# version_1_3.net
KiCad netlist of a schematic drawn in EAGLE
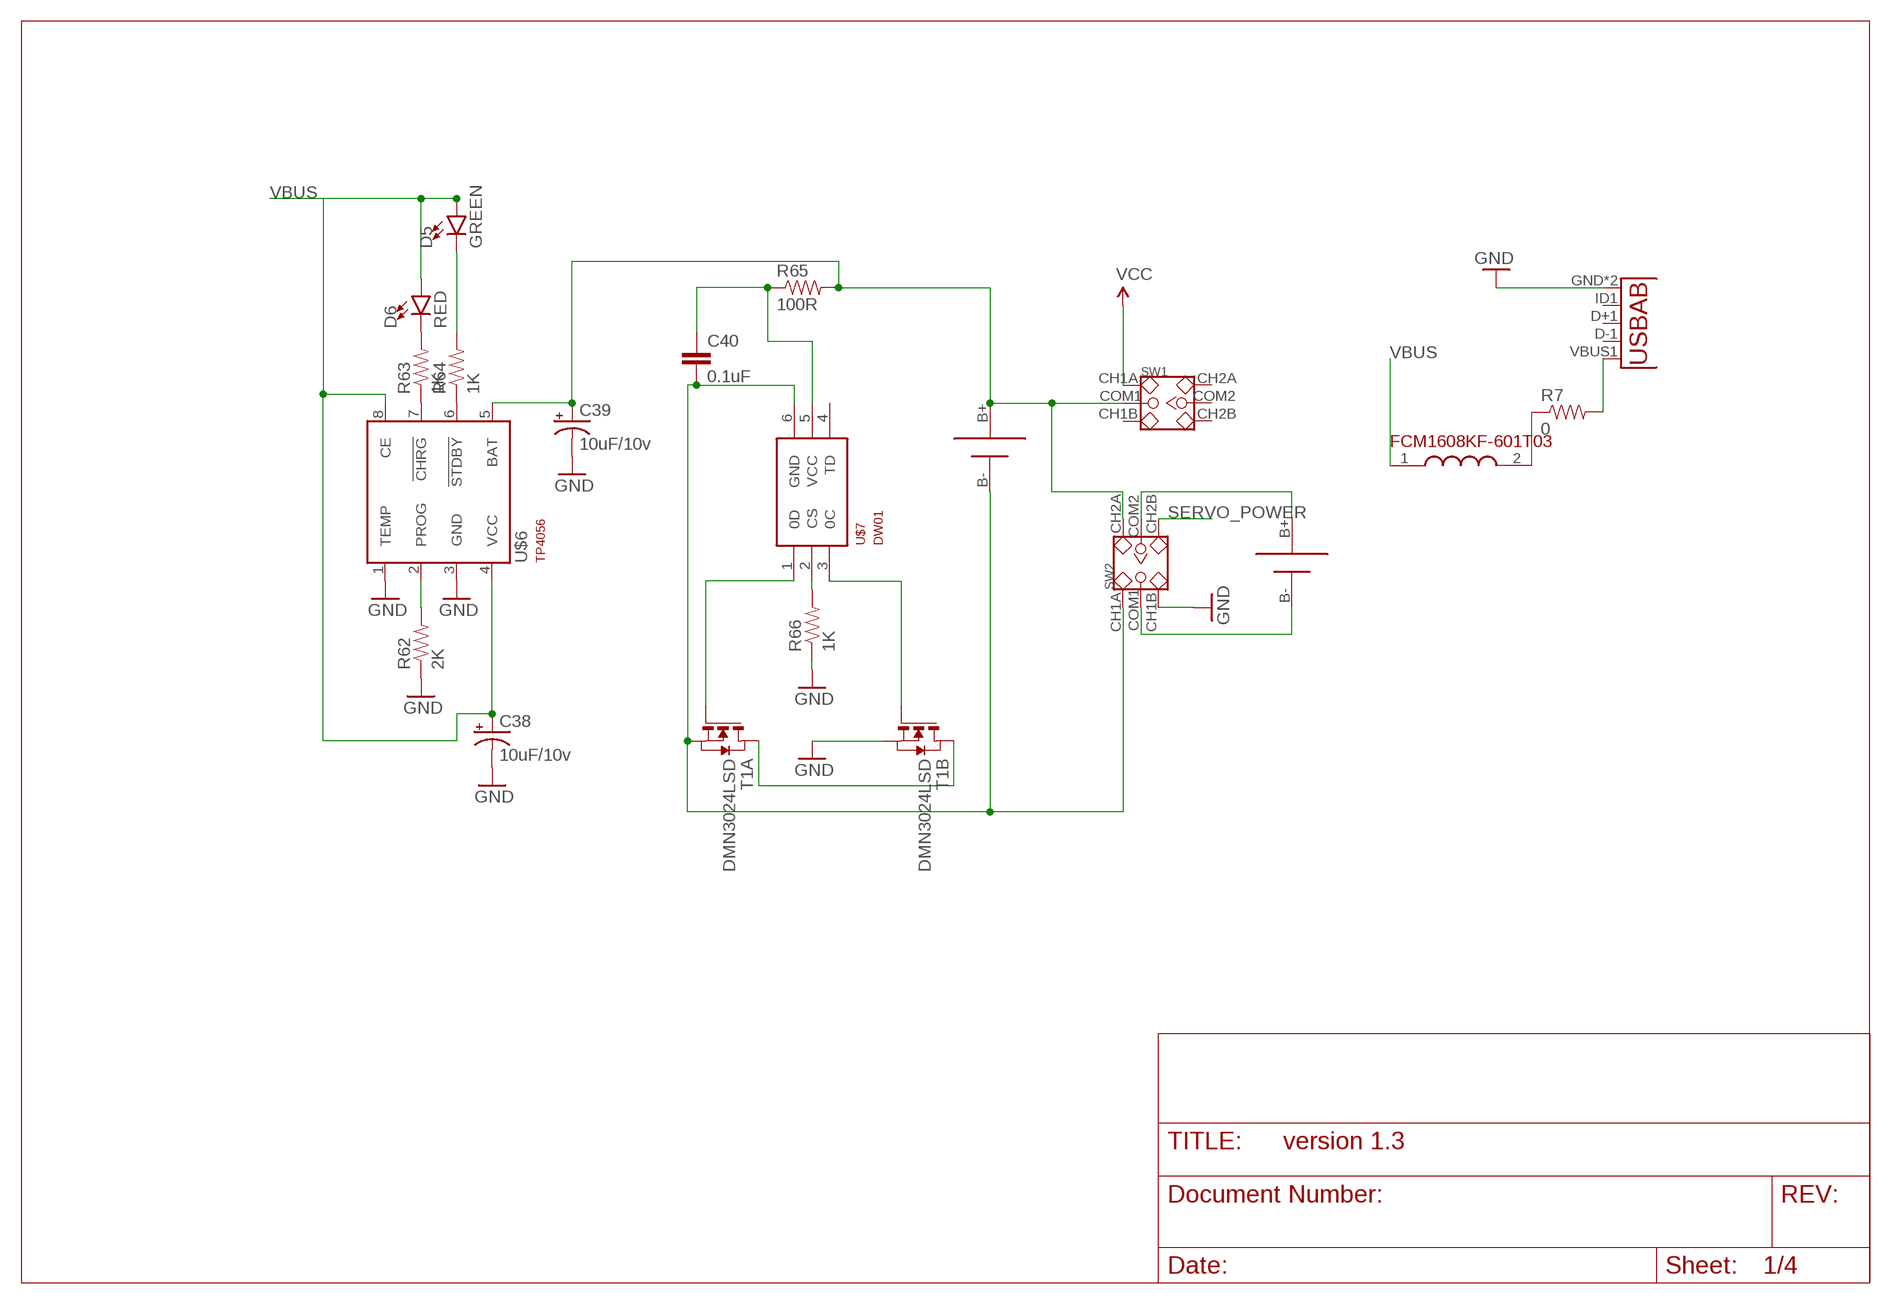
[diagram p0: schematic, sheet 1]
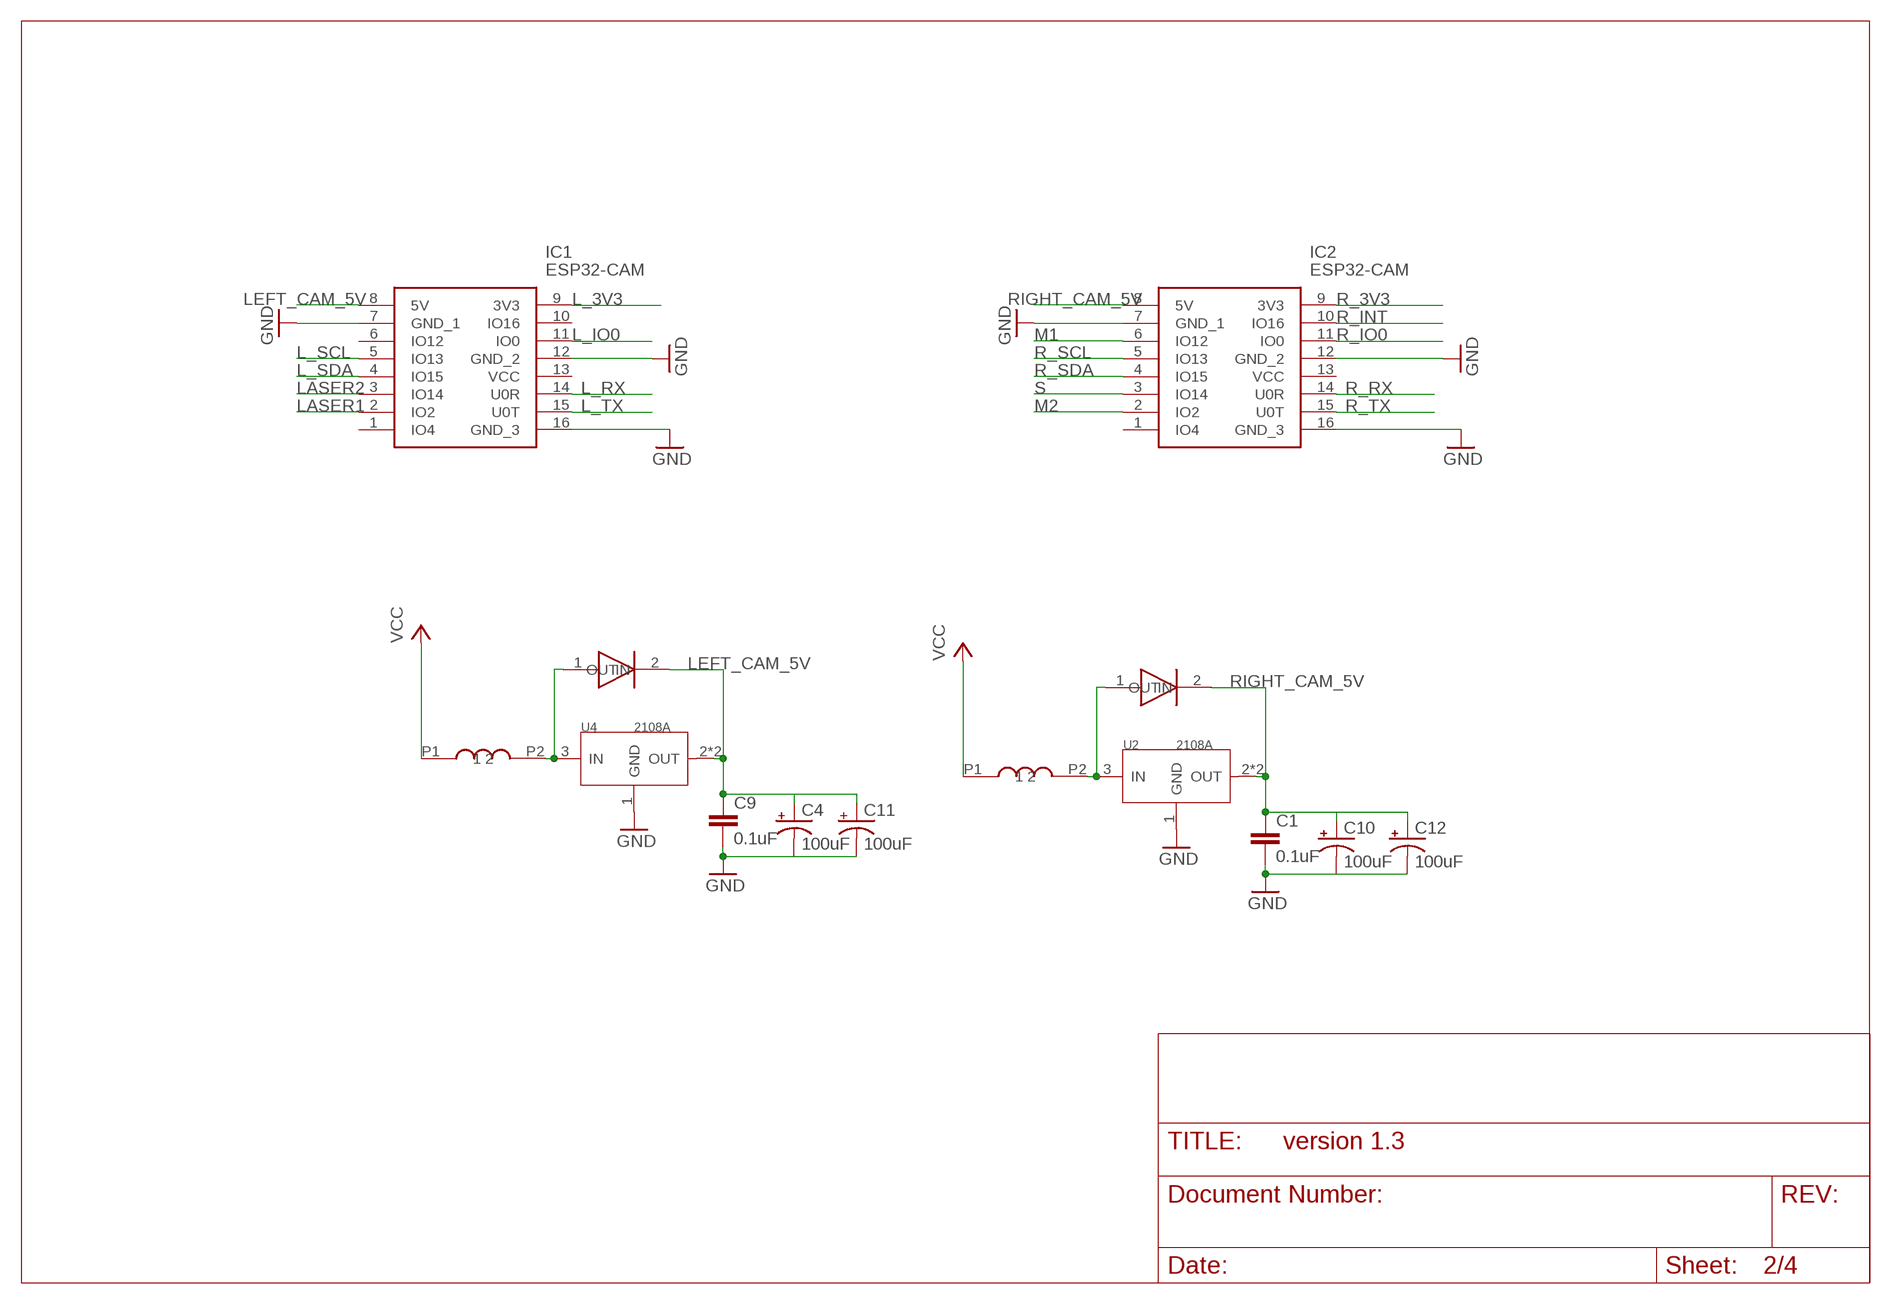
[diagram p1: schematic, sheet 2]
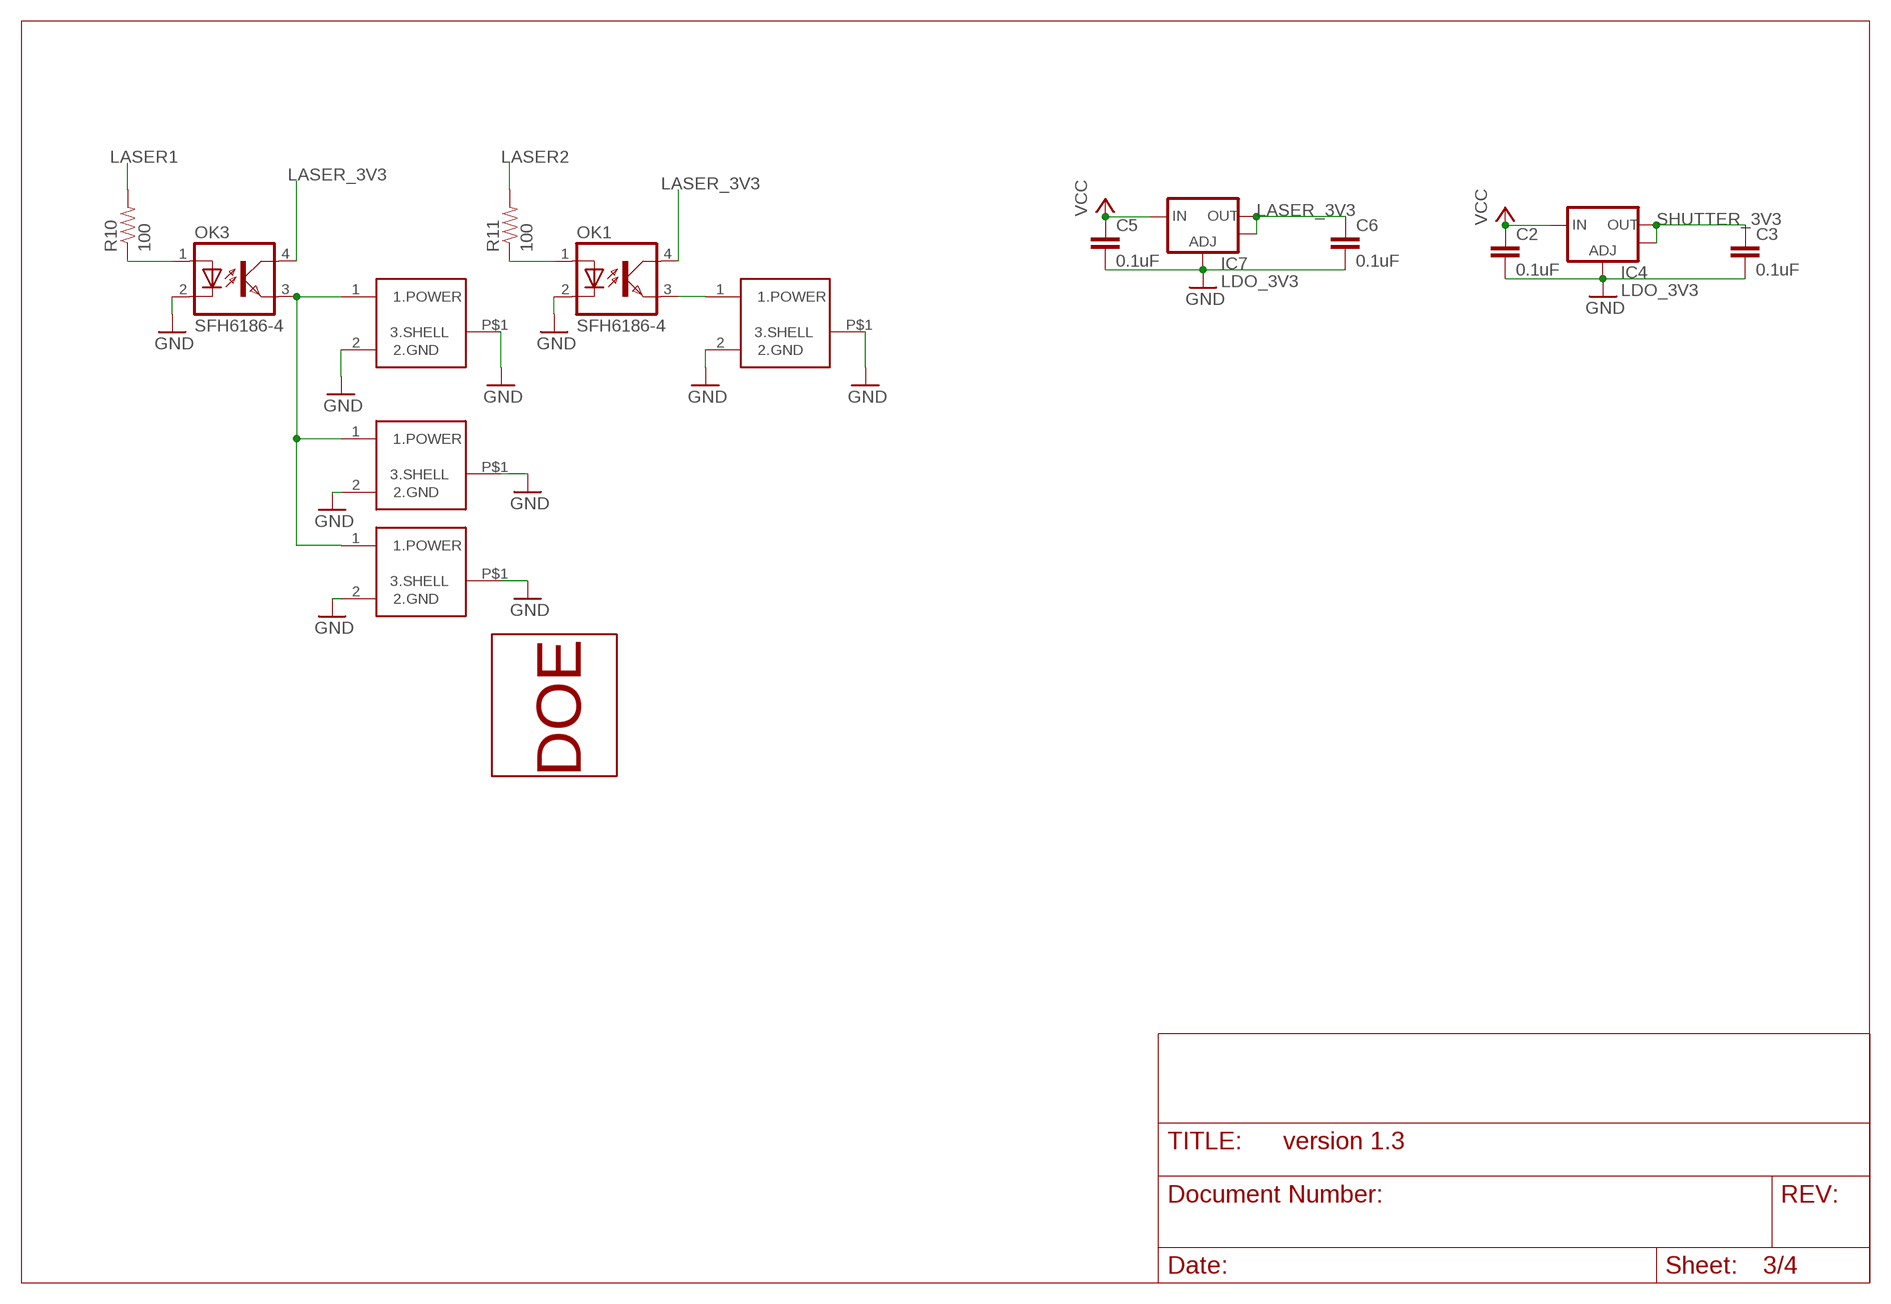
[diagram p2: schematic, sheet 3]
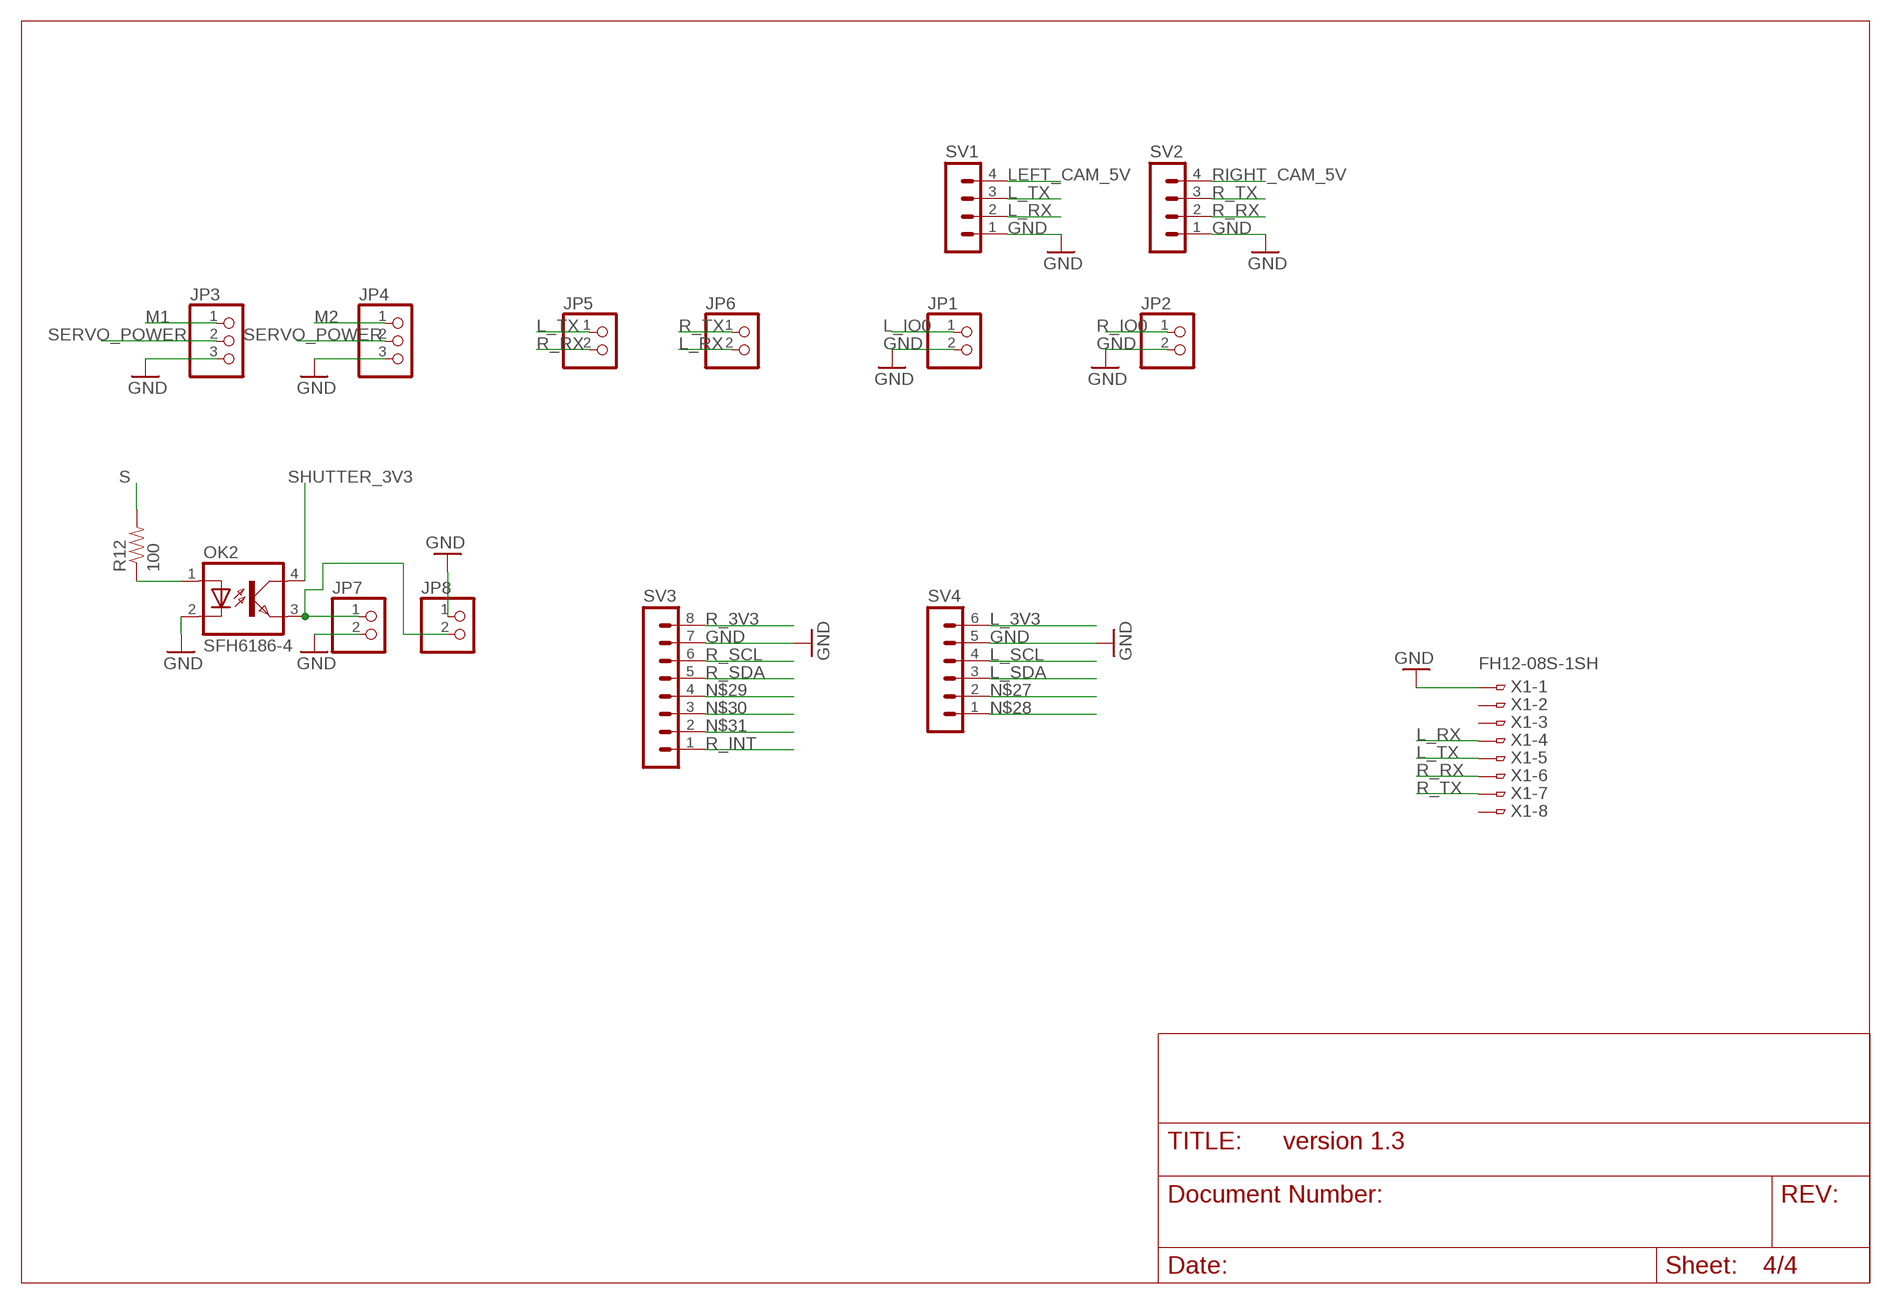
[diagram p3: schematic, sheet 4]

(export (version "E")
  (design (tool "Eeschema 10.0.6"))
  (components
    (comp (ref "C2")
      (value "0.1uF")
      (footprint "eagle-import:0603-CAP")
      (libsource (lib "eagle-import") (part "0.1UF-100V-10%(0603)"))
    )
    (comp (ref "C3")
      (value "0.1uF")
      (footprint "eagle-import:0603-CAP")
      (libsource (lib "eagle-import") (part "0.1UF-100V-10%(0603)"))
    )
    (comp (ref "C5")
      (value "0.1uF")
      (footprint "eagle-import:0603-CAP")
      (libsource (lib "eagle-import") (part "0.1UF-100V-10%(0603)"))
    )
    (comp (ref "C6")
      (value "0.1uF")
      (footprint "eagle-import:0603-CAP")
      (libsource (lib "eagle-import") (part "0.1UF-100V-10%(0603)"))
    )
    (comp (ref "IC4")
      (value "LDO_3V3")
      (footprint "eagle-import:SOT223")
      (libsource (lib "eagle-import") (part "V_REG_LM1117SOT223"))
    )
    (comp (ref "IC7")
      (value "LDO_3V3")
      (footprint "eagle-import:SOT223")
      (libsource (lib "eagle-import") (part "V_REG_LM1117SOT223"))
    )
    (comp (ref "OK1")
      (value "SFH6186-4")
      (footprint "eagle-import:SMD4-7")
      (fields (field (name "MF") "VISHAY/TELEFUNKEN"))
      (libsource (lib "eagle-import") (part "SFH618?6-4"))
    )
    (comp (ref "OK3")
      (value "SFH6186-4")
      (footprint "eagle-import:SMD4-7")
      (fields (field (name "MF") "VISHAY/TELEFUNKEN"))
      (libsource (lib "eagle-import") (part "SFH618?6-4"))
    )
    (comp (ref "R10")
      (value "100")
      (footprint "eagle-import:0603-RES")
      (libsource (lib "eagle-import") (part "1KOHM1/10W1%(0603)"))
    )
    (comp (ref "R11")
      (value "100")
      (footprint "eagle-import:0603-RES")
      (libsource (lib "eagle-import") (part "1KOHM1/10W1%(0603)"))
    )
    (comp (ref "U$1")
      (value "OD-6.5MM-LASER")
      (footprint "eagle-import:OD-6.5MM-LASER")
      (libsource (lib "eagle-import") (part "OD-6.5MM-LASER"))
    )
    (comp (ref "U$2")
      (value "OD-6.5MM-LASER")
      (footprint "eagle-import:OD-6.5MM-LASER")
      (libsource (lib "eagle-import") (part "OD-6.5MM-LASER"))
    )
    (comp (ref "U$3")
      (value "DOE-MODULE")
      (footprint "eagle-import:DOE-MODULE")
      (libsource (lib "eagle-import") (part "DOE-MODULE"))
    )
    (comp (ref "U$9")
      (value "OD-6.5MM-LASER")
      (footprint "eagle-import:OD-6.5MM-LASER")
      (libsource (lib "eagle-import") (part "OD-6.5MM-LASER"))
    )
    (comp (ref "U$20")
      (value "OD-12MM-LASER")
      (footprint "eagle-import:OD-12MM-LASER")
      (libsource (lib "eagle-import") (part "OD-12MM-LASER"))
    )
    (comp (ref "C1")
      (value "0.1uF")
      (footprint "eagle-import:0603-CAP")
      (libsource (lib "eagle-import") (part "0.1UF-25V-5%(0603)"))
    )
    (comp (ref "C4")
      (value "100uF")
      (footprint "eagle-import:E_7260-38R")
      (libsource (lib "eagle-import") (part "CPOL-USE/7260-38R"))
    )
    (comp (ref "C9")
      (value "0.1uF")
      (footprint "eagle-import:0603-CAP")
      (libsource (lib "eagle-import") (part "0.1UF-25V-5%(0603)"))
    )
    (comp (ref "C10")
      (value "100uF")
      (footprint "eagle-import:E_7260-38R")
      (libsource (lib "eagle-import") (part "CPOL-USE/7260-38R"))
    )
    (comp (ref "C11")
      (value "100uF")
      (footprint "eagle-import:E_7260-38R")
      (libsource (lib "eagle-import") (part "CPOL-USE/7260-38R"))
    )
    (comp (ref "C12")
      (value "100uF")
      (footprint "eagle-import:E_7260-38R")
      (libsource (lib "eagle-import") (part "CPOL-USE/7260-38R"))
    )
    (comp (ref "IC1")
      (value "ESP32-CAM")
      (footprint "eagle-import:ESP32CAM")
      (libsource (lib "eagle-import") (part "ESP32-CAM"))
    )
    (comp (ref "IC2")
      (value "ESP32-CAM")
      (footprint "eagle-import:ESP32CAM")
      (libsource (lib "eagle-import") (part "ESP32-CAM"))
    )
    (comp (ref "U$13")
      (value "CD54")
      (footprint "eagle-import:CD54")
      (libsource (lib "eagle-import") (part "CD54"))
    )
    (comp (ref "U$14")
      (value "SMA-SS34")
      (footprint "eagle-import:SMA-SS34")
      (libsource (lib "eagle-import") (part "SMA-SS34"))
    )
    (comp (ref "U$15")
      (value "SMA-SS34")
      (footprint "eagle-import:SMA-SS34")
      (libsource (lib "eagle-import") (part "SMA-SS34"))
    )
    (comp (ref "U$16")
      (value "CD54")
      (footprint "eagle-import:CD54")
      (libsource (lib "eagle-import") (part "CD54"))
    )
    (comp (ref "U2")
      (value "2108A")
      (footprint "eagle-import:SOT-89")
      (fields (field (name "MPN") "CJA1117B-3.3"))
      (libsource (lib "eagle-import") (part "PMIC-CJA1117B-3.3(SOT-89)"))
    )
    (comp (ref "U4")
      (value "2108A")
      (footprint "eagle-import:SOT-89")
      (fields (field (name "MPN") "CJA1117B-3.3"))
      (libsource (lib "eagle-import") (part "PMIC-CJA1117B-3.3(SOT-89)"))
    )
    (comp (ref "C38")
      (value "10uF/10v")
      (footprint "eagle-import:EIA3216-KIT")
      (libsource (lib "eagle-import") (part "CAP_POL1206-KIT"))
    )
    (comp (ref "C39")
      (value "10uF/10v")
      (footprint "eagle-import:EIA3216-KIT")
      (libsource (lib "eagle-import") (part "CAP_POL1206-KIT"))
    )
    (comp (ref "C40")
      (value "0.1uF")
      (footprint "eagle-import:0603-CAP")
      (libsource (lib "eagle-import") (part "0.1UF-100V-10%(0603)"))
    )
    (comp (ref "D5")
      (value "GREEN")
      (footprint "eagle-import:LED-0603")
      (libsource (lib "eagle-import") (part "LED-BLUE0603"))
    )
    (comp (ref "D6")
      (value "RED")
      (footprint "eagle-import:LED-0603")
      (libsource (lib "eagle-import") (part "LED-BLUE0603"))
    )
    (comp (ref "R7")
      (value "0")
      (footprint "eagle-import:0805")
      (libsource (lib "eagle-import") (part "RESISTOR0805-RES"))
    )
    (comp (ref "R62")
      (value "2K")
      (footprint "eagle-import:0603-RES")
      (libsource (lib "eagle-import") (part "1KOHM1/10W1%(0603)"))
    )
    (comp (ref "R63")
      (value "1K")
      (footprint "eagle-import:0603-RES")
      (libsource (lib "eagle-import") (part "1KOHM1/10W1%(0603)"))
    )
    (comp (ref "R64")
      (value "1K")
      (footprint "eagle-import:0603-RES")
      (libsource (lib "eagle-import") (part "1KOHM1/10W1%(0603)"))
    )
    (comp (ref "R65")
      (value "100R")
      (footprint "eagle-import:0603-RES")
      (libsource (lib "eagle-import") (part "1KOHM1/10W1%(0603)"))
    )
    (comp (ref "R66")
      (value "1K")
      (footprint "eagle-import:0603-RES")
      (libsource (lib "eagle-import") (part "1KOHM1/10W1%(0603)"))
    )
    (comp (ref "SW1")
      (value "SMD-TOGGLE-SWITCH-2CH(2X3P-7X3.5MM)")
      (footprint "eagle-import:SW6-2.54-SMD-7.0X3.5X1.5MM")
      (libsource (lib "eagle-import") (part "SMD-TOGGLE-SWITCH-2CH(2X3P-7X3.5MM)"))
    )
    (comp (ref "SW2")
      (value "SMD-TOGGLE-SWITCH-2CH(2X3P-7X3.5MM)")
      (footprint "eagle-import:SW6-2.54-SMD-7.0X3.5X1.5MM")
      (libsource (lib "eagle-import") (part "SMD-TOGGLE-SWITCH-2CH(2X3P-7X3.5MM)"))
    )
    (comp (ref "T1")
      (value "DMN3024LSD")
      (footprint "eagle-import:TSSOP-8")
      (libsource (lib "eagle-import") (part "DMN3024LSD"))
    )
    (comp (ref "U$4")
      (value "FCM1608KF-601T03")
      (footprint "eagle-import:FCM1608KF-601T03")
      (libsource (lib "eagle-import") (part "FCM1608KF-601T03"))
    )
    (comp (ref "U$5")
      (value "18650SMD")
      (footprint "eagle-import:18650SMD")
      (libsource (lib "eagle-import") (part "18650SMD"))
    )
    (comp (ref "U$6")
      (value "TP4056")
      (footprint "eagle-import:SOT23-8")
      (libsource (lib "eagle-import") (part "TP4056"))
    )
    (comp (ref "U$7")
      (value "DW01")
      (footprint "eagle-import:SOT23-6")
      (libsource (lib "eagle-import") (part "DW01"))
    )
    (comp (ref "U$8")
      (value "18650SMD")
      (footprint "eagle-import:18650SMD")
      (libsource (lib "eagle-import") (part "18650SMD"))
    )
    (comp (ref "U1")
      (value "USB\"\"")
      (footprint "eagle-import:USB-MICRO-SMD")
      (libsource (lib "eagle-import") (part "USB{dblquote}{dblquote}"))
    )
    (comp (ref "JP1")
      (value "PINHD-1X2")
      (footprint "eagle-import:1X02")
      (libsource (lib "eagle-import") (part "PINHD-1X2"))
    )
    (comp (ref "JP2")
      (value "PINHD-1X2")
      (footprint "eagle-import:1X02")
      (libsource (lib "eagle-import") (part "PINHD-1X2"))
    )
    (comp (ref "JP3")
      (value "PINHD-1X3")
      (footprint "eagle-import:1X03")
      (libsource (lib "eagle-import") (part "PINHD-1X3"))
    )
    (comp (ref "JP4")
      (value "PINHD-1X3")
      (footprint "eagle-import:1X03")
      (libsource (lib "eagle-import") (part "PINHD-1X3"))
    )
    (comp (ref "JP5")
      (value "PINHD-1X2")
      (footprint "eagle-import:1X02")
      (libsource (lib "eagle-import") (part "PINHD-1X2"))
    )
    (comp (ref "JP6")
      (value "PINHD-1X2")
      (footprint "eagle-import:1X02")
      (libsource (lib "eagle-import") (part "PINHD-1X2"))
    )
    (comp (ref "JP7")
      (value "PINHD-1X2")
      (footprint "eagle-import:1X02")
      (libsource (lib "eagle-import") (part "PINHD-1X2"))
    )
    (comp (ref "JP8")
      (value "PINHD-1X2")
      (footprint "eagle-import:1X02")
      (libsource (lib "eagle-import") (part "PINHD-1X2"))
    )
    (comp (ref "OK2")
      (value "SFH6186-4")
      (footprint "eagle-import:SMD4-7")
      (fields (field (name "MF") "VISHAY/TELEFUNKEN"))
      (libsource (lib "eagle-import") (part "SFH618?6-4"))
    )
    (comp (ref "R12")
      (value "100")
      (footprint "eagle-import:0603-RES")
      (libsource (lib "eagle-import") (part "1KOHM1/10W1%(0603)"))
    )
    (comp (ref "SV1")
      (value "MA04-1")
      (footprint "eagle-import:MA04-1")
      (libsource (lib "eagle-import") (part "MA04-1"))
    )
    (comp (ref "SV2")
      (value "MA04-1")
      (footprint "eagle-import:MA04-1")
      (libsource (lib "eagle-import") (part "MA04-1"))
    )
    (comp (ref "SV3")
      (value "MA08-1")
      (footprint "eagle-import:MA08-1")
      (libsource (lib "eagle-import") (part "MA08-1"))
    )
    (comp (ref "SV4")
      (value "MA06-1")
      (footprint "eagle-import:MA06-1")
      (libsource (lib "eagle-import") (part "MA06-1"))
    )
    (comp (ref "X1")
      (value "FH12-08S-1SH")
      (footprint "eagle-import:FH12-08S-1SH")
      (libsource (lib "eagle-import") (part "FH12-08S-1SH"))
    )
  )
  (nets
    (net (code "1") (name "GND") (class "Default")
      (node (ref "C1") (pin "2") (pinfunction "2_2") (pintype "passive"))
      (node (ref "C10") (pin "-") (pinfunction "-_-") (pintype "passive"))
      (node (ref "C11") (pin "-") (pinfunction "-_-") (pintype "passive"))
      (node (ref "C12") (pin "-") (pinfunction "-_-") (pintype "passive"))
      (node (ref "C2") (pin "2") (pinfunction "2_2") (pintype "passive"))
      (node (ref "C3") (pin "2") (pinfunction "2_2") (pintype "passive"))
      (node (ref "C38") (pin "C") (pinfunction "-_C") (pintype "passive"))
      (node (ref "C39") (pin "C") (pinfunction "-_C") (pintype "passive"))
      (node (ref "C4") (pin "-") (pinfunction "-_-") (pintype "passive"))
      (node (ref "C5") (pin "2") (pinfunction "2_2") (pintype "passive"))
      (node (ref "C6") (pin "2") (pinfunction "2_2") (pintype "passive"))
      (node (ref "C9") (pin "2") (pinfunction "2_2") (pintype "passive"))
      (node (ref "IC1") (pin "12") (pinfunction "GND_2_12") (pintype "bidirectional"))
      (node (ref "IC1") (pin "16") (pinfunction "GND_3_16") (pintype "bidirectional"))
      (node (ref "IC1") (pin "7") (pinfunction "GND_1_7") (pintype "bidirectional"))
      (node (ref "IC2") (pin "12") (pinfunction "GND_2_12") (pintype "bidirectional"))
      (node (ref "IC2") (pin "16") (pinfunction "GND_3_16") (pintype "bidirectional"))
      (node (ref "IC2") (pin "7") (pinfunction "GND_1_7") (pintype "bidirectional"))
      (node (ref "IC4") (pin "1") (pinfunction "ADJ_1") (pintype "input"))
      (node (ref "IC7") (pin "1") (pinfunction "ADJ_1") (pintype "input"))
      (node (ref "JP1") (pin "2") (pinfunction "2_2") (pintype "passive"))
      (node (ref "JP2") (pin "2") (pinfunction "2_2") (pintype "passive"))
      (node (ref "JP3") (pin "3") (pinfunction "3_3") (pintype "passive"))
      (node (ref "JP4") (pin "3") (pinfunction "3_3") (pintype "passive"))
      (node (ref "JP7") (pin "2") (pinfunction "2_2") (pintype "passive"))
      (node (ref "JP8") (pin "1") (pinfunction "1_1") (pintype "passive"))
      (node (ref "OK1") (pin "2") (pinfunction "C_2") (pintype "passive"))
      (node (ref "OK2") (pin "2") (pinfunction "C_2") (pintype "passive"))
      (node (ref "OK3") (pin "2") (pinfunction "C_2") (pintype "passive"))
      (node (ref "R62") (pin "1") (pinfunction "1_1") (pintype "passive"))
      (node (ref "R66") (pin "1") (pinfunction "1_1") (pintype "passive"))
      (node (ref "SV1") (pin "1") (pinfunction "1_1") (pintype "passive"))
      (node (ref "SV2") (pin "1") (pinfunction "1_1") (pintype "passive"))
      (node (ref "SV3") (pin "7") (pinfunction "7_7") (pintype "passive"))
      (node (ref "SV4") (pin "5") (pinfunction "5_5") (pintype "passive"))
      (node (ref "SW2") (pin "CH1B") (pinfunction "CH1B_CH1B") (pintype "bidirectional"))
      (node (ref "T1") (pin "6") (pinfunction "S_6") (pintype "passive"))
      (node (ref "T1") (pin "7") (pinfunction "S_7") (pintype "passive"))
      (node (ref "U$1") (pin "2") (pinfunction "2.GND_2") (pintype "bidirectional"))
      (node (ref "U$1") (pin "P$1") (pinfunction "3.SHELL_P$1") (pintype "bidirectional"))
      (node (ref "U$2") (pin "2") (pinfunction "2.GND_2") (pintype "bidirectional"))
      (node (ref "U$2") (pin "P$1") (pinfunction "3.SHELL_P$1") (pintype "bidirectional"))
      (node (ref "U$20") (pin "2") (pinfunction "2.GND_2") (pintype "bidirectional"))
      (node (ref "U$20") (pin "P$1") (pinfunction "3.SHELL_P$1") (pintype "bidirectional"))
      (node (ref "U$6") (pin "1") (pinfunction "TEMP_1") (pintype "bidirectional"))
      (node (ref "U$6") (pin "3") (pinfunction "GND_3") (pintype "bidirectional"))
      (node (ref "U$9") (pin "2") (pinfunction "2.GND_2") (pintype "bidirectional"))
      (node (ref "U$9") (pin "P$1") (pinfunction "3.SHELL_P$1") (pintype "bidirectional"))
      (node (ref "U1") (pin "GND") (pinfunction "GND_GND") (pintype "bidirectional"))
      (node (ref "U1") (pin "GND1") (pinfunction "GND_GND1") (pintype "bidirectional"))
      (node (ref "U2") (pin "1") (pinfunction "GND_1") (pintype "bidirectional"))
      (node (ref "U4") (pin "1") (pinfunction "GND_1") (pintype "bidirectional"))
      (node (ref "X1") (pin "1") (pinfunction "1_1") (pintype "passive"))
    )
    (net (code "2") (name "LASER1") (class "Default")
      (node (ref "IC1") (pin "2") (pinfunction "IO2_2") (pintype "bidirectional"))
      (node (ref "R10") (pin "2") (pinfunction "2_2") (pintype "passive"))
    )
    (net (code "3") (name "LASER2") (class "Default")
      (node (ref "IC1") (pin "3") (pinfunction "IO14_3") (pintype "bidirectional"))
      (node (ref "R11") (pin "2") (pinfunction "2_2") (pintype "passive"))
    )
    (net (code "4") (name "LASER_3V3") (class "Default")
      (node (ref "C6") (pin "1") (pinfunction "1_1") (pintype "passive"))
      (node (ref "IC7") (pin "2") (pinfunction "OUT_2") (pintype "output"))
      (node (ref "IC7") (pin "4") (pinfunction "OUT_4") (pintype "output"))
      (node (ref "OK1") (pin "4") (pinfunction "COL_4") (pintype "passive"))
      (node (ref "OK3") (pin "4") (pinfunction "COL_4") (pintype "passive"))
    )
    (net (code "5") (name "LEFT_CAM_5V") (class "Default")
      (node (ref "C11") (pin "+") (pinfunction "+_+") (pintype "passive"))
      (node (ref "C4") (pin "+") (pinfunction "+_+") (pintype "passive"))
      (node (ref "C9") (pin "1") (pinfunction "1_1") (pintype "passive"))
      (node (ref "IC1") (pin "8") (pinfunction "5V_8") (pintype "bidirectional"))
      (node (ref "SV1") (pin "4") (pinfunction "4_4") (pintype "passive"))
      (node (ref "U$14") (pin "2") (pinfunction "OUT_2") (pintype "bidirectional"))
      (node (ref "U4") (pin "2") (pinfunction "OUT_2") (pintype "bidirectional"))
      (node (ref "U4") (pin "4") (pinfunction "OUT_4") (pintype "bidirectional"))
    )
    (net (code "6") (name "L_3V3") (class "Default")
      (node (ref "IC1") (pin "9") (pinfunction "3V3_9") (pintype "bidirectional"))
      (node (ref "SV4") (pin "6") (pinfunction "6_6") (pintype "passive"))
    )
    (net (code "7") (name "L_IO0") (class "Default")
      (node (ref "IC1") (pin "11") (pinfunction "IO0_11") (pintype "bidirectional"))
      (node (ref "JP1") (pin "1") (pinfunction "1_1") (pintype "passive"))
    )
    (net (code "8") (name "L_RX") (class "Default")
      (node (ref "IC1") (pin "14") (pinfunction "U0R_14") (pintype "bidirectional"))
      (node (ref "JP6") (pin "2") (pinfunction "2_2") (pintype "passive"))
      (node (ref "SV1") (pin "2") (pinfunction "2_2") (pintype "passive"))
      (node (ref "X1") (pin "4") (pinfunction "1_4") (pintype "passive"))
    )
    (net (code "9") (name "L_SCL") (class "Default")
      (node (ref "IC1") (pin "5") (pinfunction "IO13_5") (pintype "bidirectional"))
      (node (ref "SV4") (pin "4") (pinfunction "4_4") (pintype "passive"))
    )
    (net (code "10") (name "L_SDA") (class "Default")
      (node (ref "IC1") (pin "4") (pinfunction "IO15_4") (pintype "bidirectional"))
      (node (ref "SV4") (pin "3") (pinfunction "3_3") (pintype "passive"))
    )
    (net (code "11") (name "L_TX") (class "Default")
      (node (ref "IC1") (pin "15") (pinfunction "U0T_15") (pintype "bidirectional"))
      (node (ref "JP5") (pin "1") (pinfunction "1_1") (pintype "passive"))
      (node (ref "SV1") (pin "3") (pinfunction "3_3") (pintype "passive"))
      (node (ref "X1") (pin "5") (pinfunction "1_5") (pintype "passive"))
    )
    (net (code "12") (name "M1") (class "Default")
      (node (ref "IC2") (pin "6") (pinfunction "IO12_6") (pintype "bidirectional"))
      (node (ref "JP3") (pin "1") (pinfunction "1_1") (pintype "passive"))
    )
    (net (code "13") (name "M2") (class "Default")
      (node (ref "IC2") (pin "2") (pinfunction "IO2_2") (pintype "bidirectional"))
      (node (ref "JP4") (pin "1") (pinfunction "1_1") (pintype "passive"))
    )
    (net (code "14") (name "N$27") (class "Default")
      (node (ref "SV4") (pin "2") (pinfunction "2_2") (pintype "passive"))
    )
    (net (code "15") (name "N$28") (class "Default")
      (node (ref "SV4") (pin "1") (pinfunction "1_1") (pintype "passive"))
    )
    (net (code "16") (name "N$29") (class "Default")
      (node (ref "SV3") (pin "4") (pinfunction "4_4") (pintype "passive"))
    )
    (net (code "17") (name "N$30") (class "Default")
      (node (ref "SV3") (pin "3") (pinfunction "3_3") (pintype "passive"))
    )
    (net (code "18") (name "N$31") (class "Default")
      (node (ref "SV3") (pin "2") (pinfunction "2_2") (pintype "passive"))
    )
    (net (code "19") (name "Net-(C39-+)") (class "Default")
      (node (ref "C39") (pin "A") (pinfunction "+_A") (pintype "passive"))
      (node (ref "R65") (pin "2") (pinfunction "2_2") (pintype "passive"))
      (node (ref "SW1") (pin "COM1") (pinfunction "COM1_COM1") (pintype "bidirectional"))
      (node (ref "SW2") (pin "CH2A") (pinfunction "CH2A_CH2A") (pintype "bidirectional"))
      (node (ref "U$5") (pin "B+") (pinfunction "B+_B+") (pintype "bidirectional"))
      (node (ref "U$6") (pin "5") (pinfunction "BAT_5") (pintype "bidirectional"))
    )
    (net (code "20") (name "Net-(D5-PadC)") (class "Default")
      (node (ref "D5") (pin "C") (pinfunction "C_C") (pintype "passive"))
      (node (ref "R64") (pin "2") (pinfunction "2_2") (pintype "passive"))
    )
    (net (code "21") (name "Net-(D6-PadC)") (class "Default")
      (node (ref "D6") (pin "C") (pinfunction "C_C") (pintype "passive"))
      (node (ref "R63") (pin "2") (pinfunction "2_2") (pintype "passive"))
    )
    (net (code "22") (name "Net-(OK1-A)") (class "Default")
      (node (ref "OK1") (pin "1") (pinfunction "A_1") (pintype "passive"))
      (node (ref "R11") (pin "1") (pinfunction "1_1") (pintype "passive"))
    )
    (net (code "23") (name "Net-(OK1-EMIT)") (class "Default")
      (node (ref "OK1") (pin "3") (pinfunction "EMIT_3") (pintype "passive"))
      (node (ref "U$20") (pin "1") (pinfunction "1.POWER_1") (pintype "bidirectional"))
    )
    (net (code "24") (name "Net-(OK2-A)") (class "Default")
      (node (ref "OK2") (pin "1") (pinfunction "A_1") (pintype "passive"))
      (node (ref "R12") (pin "1") (pinfunction "1_1") (pintype "passive"))
    )
    (net (code "25") (name "Net-(OK2-EMIT)") (class "Default")
      (node (ref "JP7") (pin "1") (pinfunction "1_1") (pintype "passive"))
      (node (ref "JP8") (pin "2") (pinfunction "2_2") (pintype "passive"))
      (node (ref "OK2") (pin "3") (pinfunction "EMIT_3") (pintype "passive"))
    )
    (net (code "26") (name "Net-(OK3-A)") (class "Default")
      (node (ref "OK3") (pin "1") (pinfunction "A_1") (pintype "passive"))
      (node (ref "R10") (pin "1") (pinfunction "1_1") (pintype "passive"))
    )
    (net (code "27") (name "Net-(OK3-EMIT)") (class "Default")
      (node (ref "OK3") (pin "3") (pinfunction "EMIT_3") (pintype "passive"))
      (node (ref "U$1") (pin "1") (pinfunction "1.POWER_1") (pintype "bidirectional"))
      (node (ref "U$2") (pin "1") (pinfunction "1.POWER_1") (pintype "bidirectional"))
      (node (ref "U$9") (pin "1") (pinfunction "1.POWER_1") (pintype "bidirectional"))
    )
    (net (code "28") (name "Net-(SW2-PadCOM1)") (class "Default")
      (node (ref "SW2") (pin "COM1") (pinfunction "COM1_COM1") (pintype "bidirectional"))
      (node (ref "U$8") (pin "B-") (pinfunction "B-_B-") (pintype "bidirectional"))
    )
    (net (code "29") (name "Net-(SW2-PadCOM2)") (class "Default")
      (node (ref "SW2") (pin "COM2") (pinfunction "COM2_COM2") (pintype "bidirectional"))
      (node (ref "U$8") (pin "B+") (pinfunction "B+_B+") (pintype "bidirectional"))
    )
    (net (code "30") (name "Net-(T1A-D)") (class "Default")
      (node (ref "T1") (pin "1") (pinfunction "D_1") (pintype "passive"))
      (node (ref "T1") (pin "8") (pinfunction "D_8") (pintype "passive"))
    )
    (net (code "31") (name "Net-(T1A-G)") (class "Default")
      (node (ref "T1") (pin "4") (pinfunction "G_4") (pintype "passive"))
      (node (ref "U$7") (pin "1") (pinfunction "0D_1") (pintype "bidirectional"))
    )
    (net (code "32") (name "Net-(T1B-G)") (class "Default")
      (node (ref "T1") (pin "5") (pinfunction "G_5") (pintype "passive"))
      (node (ref "U$7") (pin "3") (pinfunction "0C_3") (pintype "bidirectional"))
    )
    (net (code "33") (name "Net-(U$4-2.OUT)") (class "Default")
      (node (ref "R7") (pin "1") (pinfunction "1_1") (pintype "passive"))
      (node (ref "U$4") (pin "2") (pinfunction "2.OUT_2") (pintype "bidirectional"))
    )
    (net (code "34") (name "Net-(U$6-PROG)") (class "Default")
      (node (ref "R62") (pin "2") (pinfunction "2_2") (pintype "passive"))
      (node (ref "U$6") (pin "2") (pinfunction "PROG_2") (pintype "bidirectional"))
    )
    (net (code "35") (name "Net-(U$6-~{CHRG})") (class "Default")
      (node (ref "R63") (pin "1") (pinfunction "1_1") (pintype "passive"))
      (node (ref "U$6") (pin "7") (pinfunction "~{CHRG}_7") (pintype "bidirectional"))
    )
    (net (code "36") (name "Net-(U$6-~{STDBY})") (class "Default")
      (node (ref "R64") (pin "1") (pinfunction "1_1") (pintype "passive"))
      (node (ref "U$6") (pin "6") (pinfunction "~{STDBY}_6") (pintype "bidirectional"))
    )
    (net (code "37") (name "Net-(U$7-CS)") (class "Default")
      (node (ref "R66") (pin "2") (pinfunction "2_2") (pintype "passive"))
      (node (ref "U$7") (pin "2") (pinfunction "CS_2") (pintype "bidirectional"))
    )
    (net (code "38") (name "Net-(U$7-GND)") (class "Default")
      (node (ref "C40") (pin "2") (pinfunction "2_2") (pintype "passive"))
      (node (ref "SW2") (pin "CH1A") (pinfunction "CH1A_CH1A") (pintype "bidirectional"))
      (node (ref "T1") (pin "2") (pinfunction "S_2") (pintype "passive"))
      (node (ref "T1") (pin "3") (pinfunction "S_3") (pintype "passive"))
      (node (ref "U$5") (pin "B-") (pinfunction "B-_B-") (pintype "bidirectional"))
      (node (ref "U$7") (pin "6") (pinfunction "GND_6") (pintype "bidirectional"))
    )
    (net (code "39") (name "Net-(U$7-VCC)") (class "Default")
      (node (ref "C40") (pin "1") (pinfunction "1_1") (pintype "passive"))
      (node (ref "R65") (pin "1") (pinfunction "1_1") (pintype "passive"))
      (node (ref "U$7") (pin "5") (pinfunction "VCC_5") (pintype "bidirectional"))
    )
    (net (code "40") (name "Net-(U$13-2)") (class "Default")
      (node (ref "U$13") (pin "P2") (pinfunction "2_P2") (pintype "bidirectional"))
      (node (ref "U$14") (pin "1") (pinfunction "IN_1") (pintype "input"))
      (node (ref "U4") (pin "3") (pinfunction "IN_3") (pintype "bidirectional"))
    )
    (net (code "41") (name "Net-(U$15-IN)") (class "Default")
      (node (ref "U$15") (pin "1") (pinfunction "IN_1") (pintype "input"))
      (node (ref "U$16") (pin "P2") (pinfunction "2_P2") (pintype "bidirectional"))
      (node (ref "U2") (pin "3") (pinfunction "IN_3") (pintype "bidirectional"))
    )
    (net (code "42") (name "Net-(U1-VBUS)") (class "Default")
      (node (ref "R7") (pin "2") (pinfunction "2_2") (pintype "passive"))
      (node (ref "U1") (pin "VBUS1") (pinfunction "VBUS_VBUS1") (pintype "bidirectional"))
    )
    (net (code "43") (name "RIGHT_CAM_5V") (class "Default")
      (node (ref "C1") (pin "1") (pinfunction "1_1") (pintype "passive"))
      (node (ref "C10") (pin "+") (pinfunction "+_+") (pintype "passive"))
      (node (ref "C12") (pin "+") (pinfunction "+_+") (pintype "passive"))
      (node (ref "IC2") (pin "8") (pinfunction "5V_8") (pintype "bidirectional"))
      (node (ref "SV2") (pin "4") (pinfunction "4_4") (pintype "passive"))
      (node (ref "U$15") (pin "2") (pinfunction "OUT_2") (pintype "bidirectional"))
      (node (ref "U2") (pin "2") (pinfunction "OUT_2") (pintype "bidirectional"))
      (node (ref "U2") (pin "4") (pinfunction "OUT_4") (pintype "bidirectional"))
    )
    (net (code "44") (name "R_3V3") (class "Default")
      (node (ref "IC2") (pin "9") (pinfunction "3V3_9") (pintype "bidirectional"))
      (node (ref "SV3") (pin "8") (pinfunction "8_8") (pintype "passive"))
    )
    (net (code "45") (name "R_INT") (class "Default")
      (node (ref "IC2") (pin "10") (pinfunction "IO16_10") (pintype "bidirectional"))
      (node (ref "SV3") (pin "1") (pinfunction "1_1") (pintype "passive"))
    )
    (net (code "46") (name "R_IO0") (class "Default")
      (node (ref "IC2") (pin "11") (pinfunction "IO0_11") (pintype "bidirectional"))
      (node (ref "JP2") (pin "1") (pinfunction "1_1") (pintype "passive"))
    )
    (net (code "47") (name "R_RX") (class "Default")
      (node (ref "IC2") (pin "14") (pinfunction "U0R_14") (pintype "bidirectional"))
      (node (ref "JP5") (pin "2") (pinfunction "2_2") (pintype "passive"))
      (node (ref "SV2") (pin "2") (pinfunction "2_2") (pintype "passive"))
      (node (ref "X1") (pin "6") (pinfunction "1_6") (pintype "passive"))
    )
    (net (code "48") (name "R_SCL") (class "Default")
      (node (ref "IC2") (pin "5") (pinfunction "IO13_5") (pintype "bidirectional"))
      (node (ref "SV3") (pin "6") (pinfunction "6_6") (pintype "passive"))
    )
    (net (code "49") (name "R_SDA") (class "Default")
      (node (ref "IC2") (pin "4") (pinfunction "IO15_4") (pintype "bidirectional"))
      (node (ref "SV3") (pin "5") (pinfunction "5_5") (pintype "passive"))
    )
    (net (code "50") (name "R_TX") (class "Default")
      (node (ref "IC2") (pin "15") (pinfunction "U0T_15") (pintype "bidirectional"))
      (node (ref "JP6") (pin "1") (pinfunction "1_1") (pintype "passive"))
      (node (ref "SV2") (pin "3") (pinfunction "3_3") (pintype "passive"))
      (node (ref "X1") (pin "7") (pinfunction "1_7") (pintype "passive"))
    )
    (net (code "51") (name "S") (class "Default")
      (node (ref "IC2") (pin "3") (pinfunction "IO14_3") (pintype "bidirectional"))
      (node (ref "R12") (pin "2") (pinfunction "2_2") (pintype "passive"))
    )
    (net (code "52") (name "SERVO_POWER") (class "Default")
      (node (ref "JP3") (pin "2") (pinfunction "2_2") (pintype "passive"))
      (node (ref "JP4") (pin "2") (pinfunction "2_2") (pintype "passive"))
      (node (ref "SW2") (pin "CH2B") (pinfunction "CH2B_CH2B") (pintype "bidirectional"))
    )
    (net (code "53") (name "SHUTTER_3V3") (class "Default")
      (node (ref "C3") (pin "1") (pinfunction "1_1") (pintype "passive"))
      (node (ref "IC4") (pin "2") (pinfunction "OUT_2") (pintype "output"))
      (node (ref "IC4") (pin "4") (pinfunction "OUT_4") (pintype "output"))
      (node (ref "OK2") (pin "4") (pinfunction "COL_4") (pintype "passive"))
    )
    (net (code "54") (name "VBUS") (class "Default")
      (node (ref "C38") (pin "A") (pinfunction "+_A") (pintype "passive"))
      (node (ref "D5") (pin "A") (pinfunction "A_A") (pintype "passive"))
      (node (ref "D6") (pin "A") (pinfunction "A_A") (pintype "passive"))
      (node (ref "U$4") (pin "1") (pinfunction "1.IN_1") (pintype "bidirectional"))
      (node (ref "U$6") (pin "4") (pinfunction "VCC_4") (pintype "bidirectional"))
      (node (ref "U$6") (pin "8") (pinfunction "CE_8") (pintype "bidirectional"))
    )
    (net (code "55") (name "VCC") (class "Default")
      (node (ref "C2") (pin "1") (pinfunction "1_1") (pintype "passive"))
      (node (ref "C5") (pin "1") (pinfunction "1_1") (pintype "passive"))
      (node (ref "IC4") (pin "3") (pinfunction "IN_3") (pintype "input"))
      (node (ref "IC7") (pin "3") (pinfunction "IN_3") (pintype "input"))
      (node (ref "SW1") (pin "CH1A") (pinfunction "CH1A_CH1A") (pintype "bidirectional"))
      (node (ref "U$13") (pin "P1") (pinfunction "1_P1") (pintype "bidirectional"))
      (node (ref "U$16") (pin "P1") (pinfunction "1_P1") (pintype "bidirectional"))
    )
    (net (code "56") (name "unconnected-(IC1-IO4-Pad1)") (class "Default")
      (node (ref "IC1") (pin "1") (pinfunction "IO4_1") (pintype "bidirectional"))
    )
    (net (code "57") (name "unconnected-(IC1-IO12-Pad6)") (class "Default")
      (node (ref "IC1") (pin "6") (pinfunction "IO12_6") (pintype "bidirectional"))
    )
    (net (code "58") (name "unconnected-(IC1-IO16-Pad10)") (class "Default")
      (node (ref "IC1") (pin "10") (pinfunction "IO16_10") (pintype "bidirectional"))
    )
    (net (code "59") (name "unconnected-(IC1-VCC-Pad13)") (class "Default")
      (node (ref "IC1") (pin "13") (pinfunction "VCC_13") (pintype "bidirectional"))
    )
    (net (code "60") (name "unconnected-(IC2-IO4-Pad1)") (class "Default")
      (node (ref "IC2") (pin "1") (pinfunction "IO4_1") (pintype "bidirectional"))
    )
    (net (code "61") (name "unconnected-(IC2-VCC-Pad13)") (class "Default")
      (node (ref "IC2") (pin "13") (pinfunction "VCC_13") (pintype "bidirectional"))
    )
    (net (code "62") (name "unconnected-(SW1-PadCH1B)") (class "Default")
      (node (ref "SW1") (pin "CH1B") (pinfunction "CH1B_CH1B") (pintype "bidirectional"))
    )
    (net (code "63") (name "unconnected-(SW1-PadCH2A)") (class "Default")
      (node (ref "SW1") (pin "CH2A") (pinfunction "CH2A_CH2A") (pintype "bidirectional"))
    )
    (net (code "64") (name "unconnected-(SW1-PadCH2B)") (class "Default")
      (node (ref "SW1") (pin "CH2B") (pinfunction "CH2B_CH2B") (pintype "bidirectional"))
    )
    (net (code "65") (name "unconnected-(SW1-PadCOM2)") (class "Default")
      (node (ref "SW1") (pin "COM2") (pinfunction "COM2_COM2") (pintype "bidirectional"))
    )
    (net (code "66") (name "unconnected-(U$7-TD-Pad4)") (class "Default")
      (node (ref "U$7") (pin "4") (pinfunction "TD_4") (pintype "bidirectional"))
    )
    (net (code "67") (name "unconnected-(U1-D+-PadD+1)") (class "Default")
      (node (ref "U1") (pin "D+1") (pinfunction "D+_D+1") (pintype "bidirectional"))
    )
    (net (code "68") (name "unconnected-(U1-D--PadD-1)") (class "Default")
      (node (ref "U1") (pin "D-1") (pinfunction "D-_D-1") (pintype "bidirectional"))
    )
    (net (code "69") (name "unconnected-(U1-USBID-PadID1)") (class "Default")
      (node (ref "U1") (pin "ID1") (pinfunction "USBID_ID1") (pintype "bidirectional"))
    )
    (net (code "70") (name "unconnected-(X1B-1-Pad2)") (class "Default")
      (node (ref "X1") (pin "2") (pinfunction "1_2") (pintype "passive"))
    )
    (net (code "71") (name "unconnected-(X1C-1-Pad3)") (class "Default")
      (node (ref "X1") (pin "3") (pinfunction "1_3") (pintype "passive"))
    )
    (net (code "72") (name "unconnected-(X1H-1-Pad8)") (class "Default")
      (node (ref "X1") (pin "8") (pinfunction "1_8") (pintype "passive"))
    )
  )
)
